# MainBoard_V100_CSP.net
KiCad netlist of a schematic drawn in Altium Designer
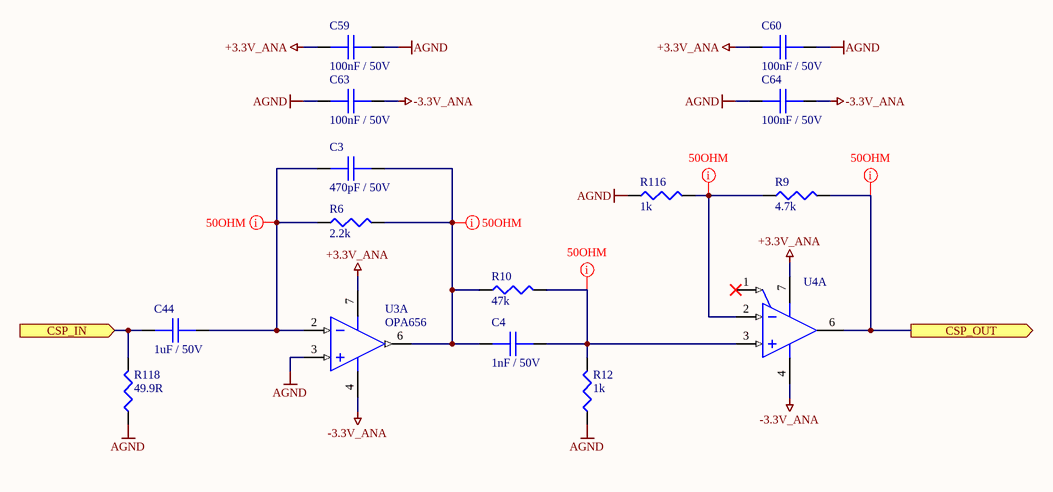
[diagram p0: MainBoard_V100_CSP.SchDoc]

(export (version "E")
  (design (tool "Eeschema 10.0.6"))
  (components
    (comp (ref "C3")
      (value "470pF / 50V")
      (footprint "0805_C")
      (description "470 pF 50V X7R")
      (fields (field (name "PART NUMBER") "SMD0805-470pF-50V"))
      (libsource (lib "ALTIUM_DB_LIB") (part "CAP_NONPOL"))
    )
    (comp (ref "C4")
      (value "1nF / 50V")
      (footprint "0805_C")
      (description "1nF 50V X7R")
      (fields (field (name "PART NUMBER") "SMD0805-1nF-50V"))
      (libsource (lib "ALTIUM_DB_LIB") (part "CAP_NONPOL"))
    )
    (comp (ref "C44")
      (value "1uF / 50V")
      (footprint "0805_C")
      (description "1uF 50V X7R")
      (fields (field (name "PART NUMBER") "SMD0805-1uF-50V"))
      (libsource (lib "ALTIUM_DB_LIB") (part "CAP_NONPOL"))
    )
    (comp (ref "C59")
      (value "100nF / 50V")
      (footprint "0805_C")
      (description "100nF 50V X7R")
      (fields (field (name "PART NUMBER") "SMD0805-100nF-50V"))
      (libsource (lib "ALTIUM_DB_LIB") (part "CAP_NONPOL"))
    )
    (comp (ref "C60")
      (value "100nF / 50V")
      (footprint "0805_C")
      (description "100nF 50V X7R")
      (fields (field (name "PART NUMBER") "SMD0805-100nF-50V"))
      (libsource (lib "ALTIUM_DB_LIB") (part "CAP_NONPOL"))
    )
    (comp (ref "C63")
      (value "100nF / 50V")
      (footprint "0805_C")
      (description "100nF 50V X7R")
      (fields (field (name "PART NUMBER") "SMD0805-100nF-50V"))
      (libsource (lib "ALTIUM_DB_LIB") (part "CAP_NONPOL"))
    )
    (comp (ref "C64")
      (value "100nF / 50V")
      (footprint "0805_C")
      (description "100nF 50V X7R")
      (fields (field (name "PART NUMBER") "SMD0805-100nF-50V"))
      (libsource (lib "ALTIUM_DB_LIB") (part "CAP_NONPOL"))
    )
    (comp (ref "R6")
      (value "2.2k")
      (footprint "0805")
      (description "2.2k 0805 0.125W 5%")
      (fields (field (name "PART NUMBER") "SMD0805-2.2k 5%"))
      (libsource (lib "ALTIUM_DB_LIB") (part "RESISTOR"))
    )
    (comp (ref "R9")
      (value "4.7k")
      (footprint "0805")
      (description "4.7k 0805 0.125W 5%")
      (fields (field (name "PART NUMBER") "SMD0805-4.7k 5%"))
      (libsource (lib "ALTIUM_DB_LIB") (part "RESISTOR"))
    )
    (comp (ref "R10")
      (value "47k")
      (footprint "0805")
      (description "47k 0805 0.125W 5%")
      (fields (field (name "PART NUMBER") "SMD0805-47k 5%"))
      (libsource (lib "ALTIUM_DB_LIB") (part "RESISTOR"))
    )
    (comp (ref "R12")
      (value "1k")
      (footprint "0805")
      (description "1k 0805 0.125W 1%")
      (fields (field (name "PART NUMBER") "SMD0805-1k 1%"))
      (libsource (lib "ALTIUM_DB_LIB") (part "RESISTOR"))
    )
    (comp (ref "R116")
      (value "1k")
      (footprint "0805")
      (description "1k 0805 0.125W 1%")
      (fields (field (name "PART NUMBER") "SMD0805-1k 1%"))
      (libsource (lib "ALTIUM_DB_LIB") (part "RESISTOR"))
    )
    (comp (ref "R118")
      (value "49.9R")
      (footprint "0805")
      (description "49.9R 0805 0.125W 1%")
      (fields (field (name "PART NUMBER") "SMD0805-49.9R 1%"))
      (libsource (lib "ALTIUM_DB_LIB") (part "RESISTOR"))
    )
    (comp (ref "U3")
      (value "OPA656")
      (footprint "SO-8")
      (fields (field (name "PARTNUMBER") "OPA656U") (field (name "MANUFACTURER") "Texas Instruments"))
      (libsource (lib "ALTIUM_DB_LIB") (part "OPA656"))
    )
    (comp (ref "U4")
      (value "LT1806CS8#PBF")
      (footprint "SO-8")
      (fields
        (field (name "MANUFACTURER") "Linear Technology")
        (field (name "LINEAR TECHNOLOGY PART NUMBER") "LT1806")
      )
      (libsource (lib "ALTIUM_DB_LIB") (part "LT1806CS8#PBF"))
    )
  )
  (nets
    (net (code "1") (name "+3.3V_ANA") (class "Default")
      (node (ref "C59") (pin "1") (pintype "passive"))
      (node (ref "C60") (pin "1") (pintype "passive"))
      (node (ref "U3") (pin "7") (pinfunction "VS+_7") (pintype "power_in"))
      (node (ref "U4") (pin "7") (pinfunction "V+_7") (pintype "power_in"))
    )
    (net (code "2") (name "-3.3V_ANA") (class "Default")
      (node (ref "C63") (pin "2") (pintype "passive"))
      (node (ref "C64") (pin "2") (pintype "passive"))
      (node (ref "U3") (pin "4") (pinfunction "VS-_4") (pintype "power_in"))
      (node (ref "U4") (pin "4") (pinfunction "V-_4") (pintype "power_in"))
    )
    (net (code "3") (name "/CSP_IN") (class "Default")
      (node (ref "C44") (pin "1") (pintype "passive"))
      (node (ref "R118") (pin "2") (pintype "passive"))
    )
    (net (code "4") (name "/CSP_OUT") (class "Default")
      (node (ref "R9") (pin "2") (pintype "passive"))
      (node (ref "U4") (pin "6") (pinfunction "OUT_6") (pintype "tri_state"))
    )
    (net (code "5") (name "AGND") (class "Default")
      (node (ref "C59") (pin "2") (pintype "passive"))
      (node (ref "C60") (pin "2") (pintype "passive"))
      (node (ref "C63") (pin "1") (pintype "passive"))
      (node (ref "C64") (pin "1") (pintype "passive"))
      (node (ref "R116") (pin "1") (pintype "passive"))
      (node (ref "R118") (pin "1") (pintype "passive"))
      (node (ref "R12") (pin "1") (pintype "passive"))
      (node (ref "U3") (pin "3") (pinfunction "IN+_3") (pintype "input"))
    )
    (net (code "6") (name "Net-(U3A-IN-)") (class "Default")
      (node (ref "C3") (pin "2") (pintype "passive"))
      (node (ref "C44") (pin "2") (pintype "passive"))
      (node (ref "R6") (pin "2") (pintype "passive"))
      (node (ref "U3") (pin "2") (pinfunction "IN-_2") (pintype "input"))
    )
    (net (code "7") (name "Net-(U3A-OUT)") (class "Default")
      (node (ref "C3") (pin "1") (pintype "passive"))
      (node (ref "C4") (pin "1") (pintype "passive"))
      (node (ref "R10") (pin "1") (pintype "passive"))
      (node (ref "R6") (pin "1") (pintype "passive"))
      (node (ref "U3") (pin "6") (pinfunction "OUT_6") (pintype "output"))
    )
    (net (code "8") (name "Net-(U4A-+IN)") (class "Default")
      (node (ref "C4") (pin "2") (pintype "passive"))
      (node (ref "R10") (pin "2") (pintype "passive"))
      (node (ref "R12") (pin "2") (pintype "passive"))
      (node (ref "U4") (pin "3") (pinfunction "+IN_3") (pintype "input"))
    )
    (net (code "9") (name "Net-(U4A--IN)") (class "Default")
      (node (ref "R116") (pin "2") (pintype "passive"))
      (node (ref "R9") (pin "1") (pintype "passive"))
      (node (ref "U4") (pin "2") (pinfunction "-IN_2") (pintype "input"))
    )
    (net (code "10") (name "unconnected-(U4A-~{SHDN}-Pad1)") (class "Default")
      (node (ref "U4") (pin "1") (pinfunction "~{SHDN}_1") (pintype "input+no_connect"))
    )
  )
)
